# 06_Reset.net
KiCad netlist of a schematic drawn in Altium Designer
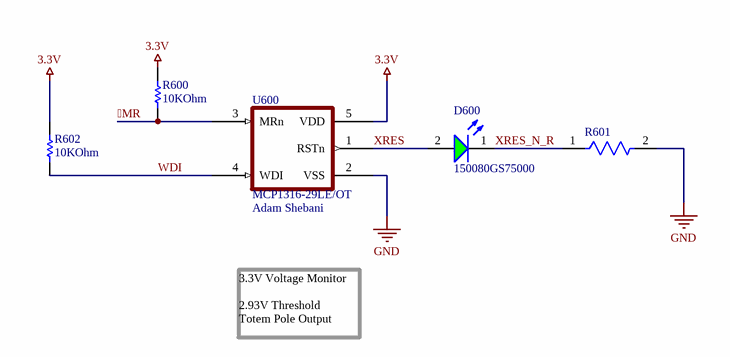
[diagram p0: 06_Reset.SchDoc]

(export (version "E")
  (design (tool "Eeschema 10.0.6"))
  (components
    (comp (ref "D600")
      (value "150080GS75000")
      (footprint "WL-SMCW_0805_150080xx75000")
      (description "WURTH ELEKTRONIK - 150080GS75000 - LED, Green, SMD, 0805, 30 mA, 3.2 V, 520 nm")
      (libsource (lib "Altium Content Vault") (part "LED_Green_2A-1K"))
    )
    (comp (ref "R600")
      (value "RC1206FR-0710KL")
      (footprint "RESC3116X65X40ML10T20")
      (description "Chip Resistor, 10 KOhm, +/- 1%, 0.25 W, -55 to 155 degC, 1206 (3216 Metric), RoHS, Tape and Reel")
      (fields
        (field (name "TOLERANCE") "1%")
        (field (name "RESISTANCE") "10KOhm")
        (field (name "MANUFACTURER") "Yageo")
      )
      (libsource (lib "Altium Content Vault") (part "RES-2"))
    )
    (comp (ref "R601")
      (value "RMCF1206JT330R")
      (footprint "FP-RMCF1206-MFG")
      (description "330Ω ±5% 0.25W 1206 Thick Film Chip Resistor AEC-Q200 compliant")
      (fields (field (name "TOLERANCE") "5%"))
      (libsource (lib "Altium Content Vault") (part "1029c3af85768c4190bb7ad29bc67b5"))
    )
    (comp (ref "R602")
      (value "RC1206FR-0710KL")
      (footprint "RESC3116X65X40ML10T20")
      (description "Chip Resistor, 10 KOhm, +/- 1%, 0.25 W, -55 to 155 degC, 1206 (3216 Metric), RoHS, Tape and Reel")
      (fields
        (field (name "TOLERANCE") "1%")
        (field (name "RESISTANCE") "10KOhm")
        (field (name "MANUFACTURER") "Yageo")
      )
      (libsource (lib "Altium Content Vault") (part "RES-2"))
    )
    (comp (ref "U600")
      (value "MCP1316-29LE/OT")
      (footprint "SOT23-5-MCP-1316T")
      (description "Pwr Sply Func; Voltage Detector, Voltage Supervisor; SOT-23; VS 1 to 5.5V; IS 10uA")
      (fields
        (field (name "MANUFACTURER") "Microchip")
        (field (name "MANUFACTURER PART NUMBER") "MCP1316T-29LE/OT")
        (field (name "DRAWN BY") "Adam Shebani")
      )
      (libsource (lib "ECE315-F25") (part "MCP1316-29LE/OT"))
    )
  )
  (nets
    (net (code "1") (name "/MR") (class "Default")
      (node (ref "R600") (pin "1") (pinfunction "1_1") (pintype "passive"))
      (node (ref "U600") (pin "3") (pinfunction "MRn_3") (pintype "input"))
    )
    (net (code "2") (name "/WDI") (class "Default")
      (node (ref "R602") (pin "1") (pinfunction "1_1") (pintype "passive"))
      (node (ref "U600") (pin "4") (pinfunction "WDI_4") (pintype "input"))
    )
    (net (code "3") (name "/XRES") (class "Default")
      (node (ref "D600") (pin "2") (pinfunction "A_2") (pintype "passive"))
      (node (ref "U600") (pin "1") (pinfunction "RSTn_1") (pintype "output"))
    )
    (net (code "4") (name "/XRES_N_R") (class "Default")
      (node (ref "D600") (pin "1") (pinfunction "K_1") (pintype "passive"))
      (node (ref "R601") (pin "1") (pinfunction "1_1") (pintype "passive"))
    )
    (net (code "5") (name "3.3V") (class "Default")
      (node (ref "R600") (pin "2") (pinfunction "2_2") (pintype "passive"))
      (node (ref "R602") (pin "2") (pinfunction "2_2") (pintype "passive"))
      (node (ref "U600") (pin "5") (pinfunction "VDD_5") (pintype "power_in"))
    )
    (net (code "6") (name "GND") (class "Default")
      (node (ref "R601") (pin "2") (pinfunction "2_2") (pintype "passive"))
      (node (ref "U600") (pin "2") (pinfunction "VSS_2") (pintype "power_in"))
    )
  )
)
